# accelerometer.net
KiCad netlist of a schematic drawn in EAGLE
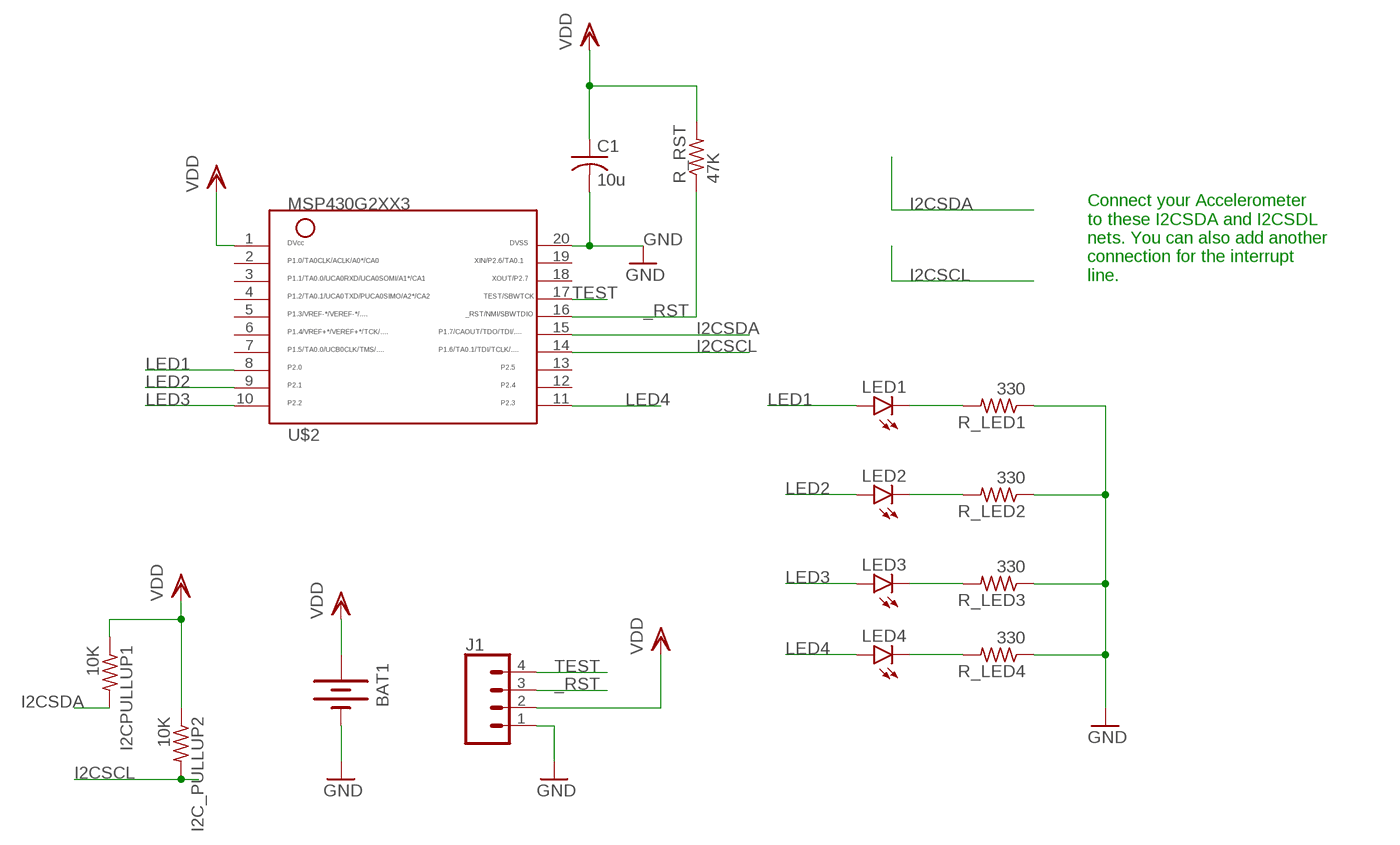
[diagram p0: schematic, sheet 1]

(export (version "E")
  (design (tool "Eeschema 10.0.6"))
  (components
    (comp (ref "BAT1")
      (value "BATTERYBU2032SM")
      (footprint "eagle-import:BU2032SM")
      (libsource (lib "eagle-import") (part "BATTERYBU2032SM"))
    )
    (comp (ref "C1")
      (value "10u")
      (footprint "eagle-import:C1206")
      (libsource (lib "eagle-import") (part "C-USC1206"))
    )
    (comp (ref "I2CPULLUP1")
      (value "10K")
      (footprint "eagle-import:R1206")
      (libsource (lib "eagle-import") (part "R-US_R1206"))
    )
    (comp (ref "I2C_PULLUP2")
      (value "10K")
      (footprint "eagle-import:R1206")
      (libsource (lib "eagle-import") (part "R-US_R1206"))
    )
    (comp (ref "J1")
      (value "CONN_04LOCK")
      (footprint "eagle-import:1X04_LOCK")
      (libsource (lib "eagle-import") (part "CONN_04LOCK"))
    )
    (comp (ref "LED1")
      (value "LEDCHIPLED_1206")
      (footprint "eagle-import:CHIPLED_1206")
      (libsource (lib "eagle-import") (part "LEDCHIPLED_1206"))
    )
    (comp (ref "LED2")
      (value "LEDCHIPLED_1206")
      (footprint "eagle-import:CHIPLED_1206")
      (libsource (lib "eagle-import") (part "LEDCHIPLED_1206"))
    )
    (comp (ref "LED3")
      (value "LEDCHIPLED_1206")
      (footprint "eagle-import:CHIPLED_1206")
      (libsource (lib "eagle-import") (part "LEDCHIPLED_1206"))
    )
    (comp (ref "LED4")
      (value "LEDCHIPLED_1206")
      (footprint "eagle-import:CHIPLED_1206")
      (libsource (lib "eagle-import") (part "LEDCHIPLED_1206"))
    )
    (comp (ref "R_LED1")
      (value "330")
      (footprint "eagle-import:R1206")
      (libsource (lib "eagle-import") (part "R-US_R1206"))
    )
    (comp (ref "R_LED2")
      (value "330")
      (footprint "eagle-import:R1206")
      (libsource (lib "eagle-import") (part "R-US_R1206"))
    )
    (comp (ref "R_LED3")
      (value "330")
      (footprint "eagle-import:R1206")
      (libsource (lib "eagle-import") (part "R-US_R1206"))
    )
    (comp (ref "R_LED4")
      (value "330")
      (footprint "eagle-import:R1206")
      (libsource (lib "eagle-import") (part "R-US_R1206"))
    )
    (comp (ref "R_RST")
      (value "47K")
      (footprint "eagle-import:R1206")
      (libsource (lib "eagle-import") (part "R-US_R1206"))
    )
    (comp (ref "U$2")
      (value "MSP430G2XX3TSSOP")
      (footprint "eagle-import:PW20")
      (libsource (lib "eagle-import") (part "MSP430G2XX3TSSOP"))
    )
  )
  (nets
    (net (code "1") (name "/I2CSCL") (class "Default")
      (node (ref "I2C_PULLUP2") (pin "2") (pinfunction "2_2") (pintype "passive"))
      (node (ref "U$2") (pin "14") (pinfunction "14_14") (pintype "bidirectional"))
    )
    (net (code "2") (name "/I2CSDA") (class "Default")
      (node (ref "I2CPULLUP1") (pin "2") (pinfunction "2_2") (pintype "passive"))
      (node (ref "U$2") (pin "15") (pinfunction "15_15") (pintype "bidirectional"))
    )
    (net (code "3") (name "/LED1") (class "Default")
      (node (ref "LED1") (pin "A") (pinfunction "A_A") (pintype "passive"))
      (node (ref "U$2") (pin "8") (pinfunction "8_8") (pintype "bidirectional"))
    )
    (net (code "4") (name "/LED2") (class "Default")
      (node (ref "LED2") (pin "A") (pinfunction "A_A") (pintype "passive"))
      (node (ref "U$2") (pin "9") (pinfunction "9_9") (pintype "bidirectional"))
    )
    (net (code "5") (name "/LED3") (class "Default")
      (node (ref "LED3") (pin "A") (pinfunction "A_A") (pintype "passive"))
      (node (ref "U$2") (pin "10") (pinfunction "10_10") (pintype "bidirectional"))
    )
    (net (code "6") (name "/LED4") (class "Default")
      (node (ref "LED4") (pin "A") (pinfunction "A_A") (pintype "passive"))
      (node (ref "U$2") (pin "11") (pinfunction "11_11") (pintype "bidirectional"))
    )
    (net (code "7") (name "/TEST") (class "Default")
      (node (ref "J1") (pin "4") (pinfunction "4_4") (pintype "passive"))
      (node (ref "U$2") (pin "17") (pinfunction "17_17") (pintype "bidirectional"))
    )
    (net (code "8") (name "/_RST") (class "Default")
      (node (ref "J1") (pin "3") (pinfunction "3_3") (pintype "passive"))
      (node (ref "R_RST") (pin "1") (pinfunction "1_1") (pintype "passive"))
      (node (ref "U$2") (pin "16") (pinfunction "16_16") (pintype "bidirectional"))
    )
    (net (code "9") (name "GND") (class "Default")
      (node (ref "BAT1") (pin "P$2") (pinfunction "-_P$2") (pintype "power_in"))
      (node (ref "C1") (pin "2") (pinfunction "2_2") (pintype "passive"))
      (node (ref "J1") (pin "1") (pinfunction "1_1") (pintype "passive"))
      (node (ref "R_LED1") (pin "1") (pinfunction "1_1") (pintype "passive"))
      (node (ref "R_LED2") (pin "1") (pinfunction "1_1") (pintype "passive"))
      (node (ref "R_LED3") (pin "1") (pinfunction "1_1") (pintype "passive"))
      (node (ref "R_LED4") (pin "1") (pinfunction "1_1") (pintype "passive"))
      (node (ref "U$2") (pin "20") (pinfunction "20_20") (pintype "bidirectional"))
    )
    (net (code "10") (name "Net-(LED1-PadC)") (class "Default")
      (node (ref "LED1") (pin "C") (pinfunction "C_C") (pintype "passive"))
      (node (ref "R_LED1") (pin "2") (pinfunction "2_2") (pintype "passive"))
    )
    (net (code "11") (name "Net-(LED2-PadC)") (class "Default")
      (node (ref "LED2") (pin "C") (pinfunction "C_C") (pintype "passive"))
      (node (ref "R_LED2") (pin "2") (pinfunction "2_2") (pintype "passive"))
    )
    (net (code "12") (name "Net-(LED3-PadC)") (class "Default")
      (node (ref "LED3") (pin "C") (pinfunction "C_C") (pintype "passive"))
      (node (ref "R_LED3") (pin "2") (pinfunction "2_2") (pintype "passive"))
    )
    (net (code "13") (name "Net-(LED4-PadC)") (class "Default")
      (node (ref "LED4") (pin "C") (pinfunction "C_C") (pintype "passive"))
      (node (ref "R_LED4") (pin "2") (pinfunction "2_2") (pintype "passive"))
    )
    (net (code "14") (name "VDD") (class "Default")
      (node (ref "BAT1") (pin "P$1") (pinfunction "+_P$1") (pintype "power_in"))
      (node (ref "C1") (pin "1") (pinfunction "1_1") (pintype "passive"))
      (node (ref "I2CPULLUP1") (pin "1") (pinfunction "1_1") (pintype "passive"))
      (node (ref "I2C_PULLUP2") (pin "1") (pinfunction "1_1") (pintype "passive"))
      (node (ref "J1") (pin "2") (pinfunction "2_2") (pintype "passive"))
      (node (ref "R_RST") (pin "2") (pinfunction "2_2") (pintype "passive"))
      (node (ref "U$2") (pin "1") (pinfunction "1_1") (pintype "bidirectional"))
    )
    (net (code "15") (name "unconnected-(U$2-Pad2)") (class "Default")
      (node (ref "U$2") (pin "2") (pinfunction "2_2") (pintype "bidirectional"))
    )
    (net (code "16") (name "unconnected-(U$2-Pad3)") (class "Default")
      (node (ref "U$2") (pin "3") (pinfunction "3_3") (pintype "bidirectional"))
    )
    (net (code "17") (name "unconnected-(U$2-Pad4)") (class "Default")
      (node (ref "U$2") (pin "4") (pinfunction "4_4") (pintype "bidirectional"))
    )
    (net (code "18") (name "unconnected-(U$2-Pad5)") (class "Default")
      (node (ref "U$2") (pin "5") (pinfunction "5_5") (pintype "bidirectional"))
    )
    (net (code "19") (name "unconnected-(U$2-Pad6)") (class "Default")
      (node (ref "U$2") (pin "6") (pinfunction "6_6") (pintype "bidirectional"))
    )
    (net (code "20") (name "unconnected-(U$2-Pad7)") (class "Default")
      (node (ref "U$2") (pin "7") (pinfunction "7_7") (pintype "bidirectional"))
    )
    (net (code "21") (name "unconnected-(U$2-Pad12)") (class "Default")
      (node (ref "U$2") (pin "12") (pinfunction "12_12") (pintype "bidirectional"))
    )
    (net (code "22") (name "unconnected-(U$2-Pad13)") (class "Default")
      (node (ref "U$2") (pin "13") (pinfunction "13_13") (pintype "bidirectional"))
    )
    (net (code "23") (name "unconnected-(U$2-Pad18)") (class "Default")
      (node (ref "U$2") (pin "18") (pinfunction "18_18") (pintype "bidirectional"))
    )
    (net (code "24") (name "unconnected-(U$2-Pad19)") (class "Default")
      (node (ref "U$2") (pin "19") (pinfunction "19_19") (pintype "bidirectional"))
    )
  )
)
